# power.net
KiCad netlist of a schematic drawn in Altium Designer
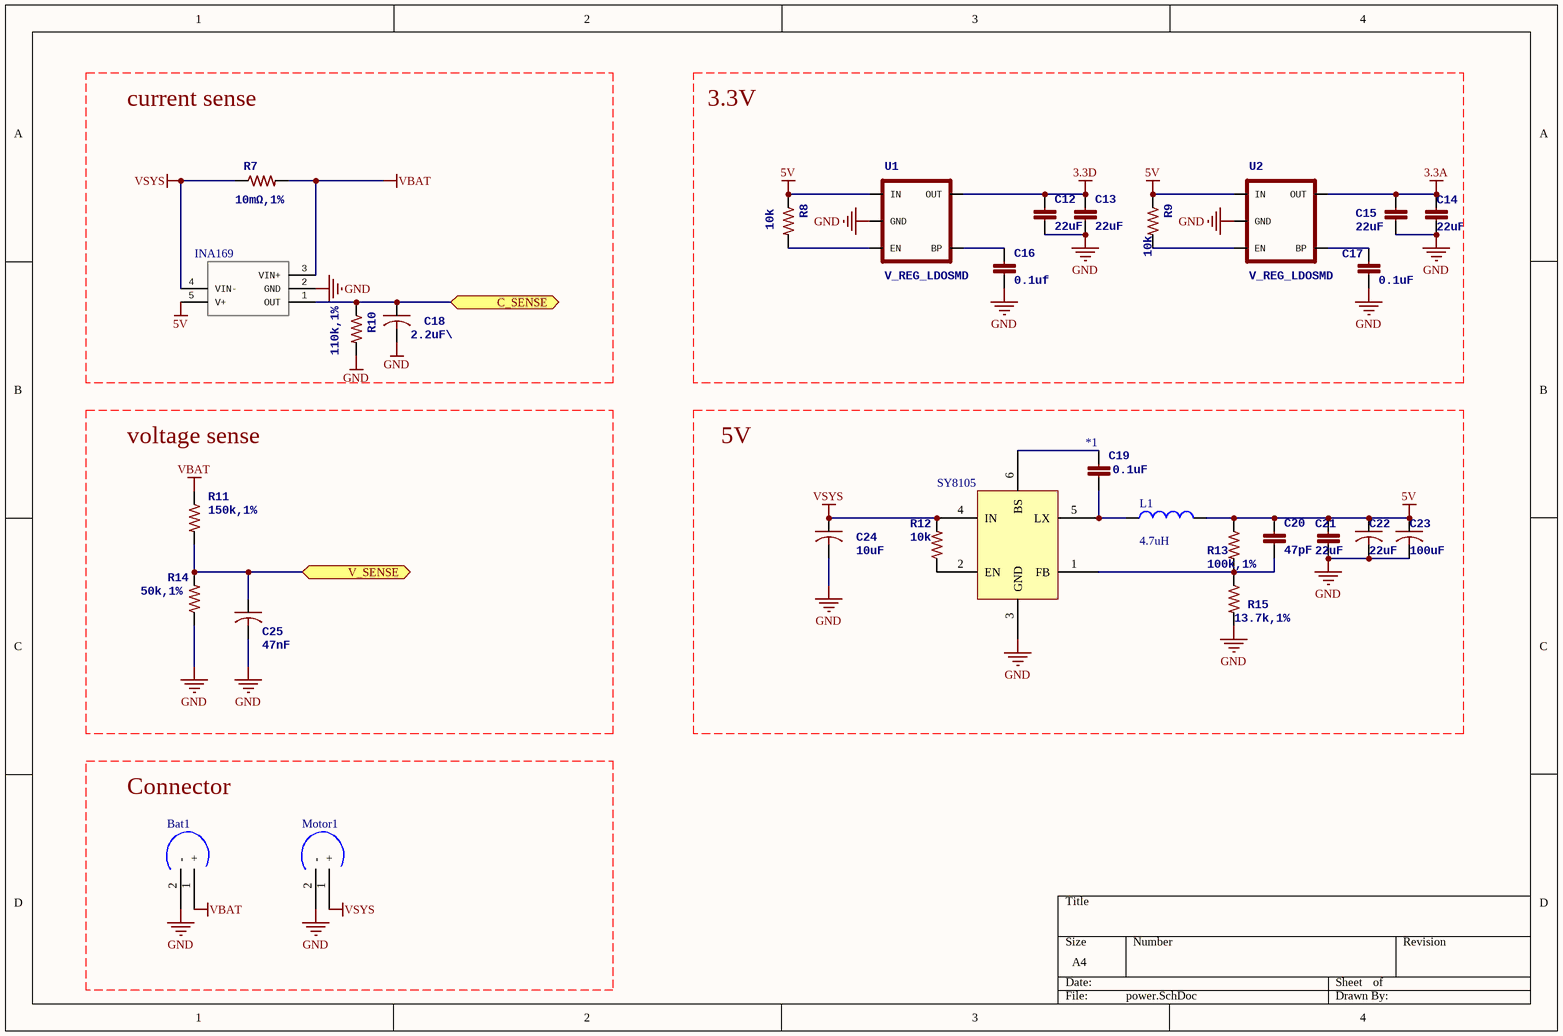
[diagram p0: power.SchDoc]

(export (version "E")
  (design (tool "Eeschema 10.0.6"))
  (components
    (comp (ref "*1") (value "SY8105") (footprint "SOT23-6") (libsource (lib "sch") (part "SY8105")))
    (comp (ref "Bat1")
      (value "Battery_AWG12")
      (footprint "Battery_AWG12")
      (libsource (lib "sch") (part "Battery_AWG12"))
    )
    (comp (ref "C12")
      (value "22uF")
      (footprint "0805")
      (description "<b>Capacitor</b>\nStandard 0603 ceramic capacitor, and 0.1\" leaded capacitor.")
      (fields (field (name "PARTNO") "CC0402ZRY5V7BB104"))
      (libsource (lib "pixhawk2") (part "CAP0402-CAP"))
    )
    (comp (ref "C13")
      (value "22uF")
      (footprint "0805")
      (description "<b>Capacitor</b>\nStandard 0603 ceramic capacitor, and 0.1\" leaded capacitor.")
      (fields (field (name "PARTNO") "CC0402ZRY5V7BB104"))
      (libsource (lib "pixhawk2") (part "CAP0402-CAP"))
    )
    (comp (ref "C14")
      (value "22uF")
      (footprint "0805")
      (description "<b>Capacitor</b>\nStandard 0603 ceramic capacitor, and 0.1\" leaded capacitor.")
      (fields (field (name "PARTNO") "CC0402ZRY5V7BB104"))
      (libsource (lib "pixhawk2") (part "CAP0402-CAP"))
    )
    (comp (ref "C15")
      (value "22uF")
      (footprint "0805")
      (description "<b>Capacitor</b>\nStandard 0603 ceramic capacitor, and 0.1\" leaded capacitor.")
      (fields (field (name "PARTNO") "CC0402ZRY5V7BB104"))
      (libsource (lib "pixhawk2") (part "CAP0402-CAP"))
    )
    (comp (ref "C16")
      (value "0.1uf")
      (footprint "0402")
      (description "<b>Capacitor</b>\nStandard 0603 ceramic capacitor, and 0.1\" leaded capacitor.")
      (fields (field (name "PARTNO") "CC0402ZRY5V7BB104"))
      (libsource (lib "pixhawk2") (part "CAP0402-CAP"))
    )
    (comp (ref "C17")
      (value "0.1uF")
      (footprint "0402")
      (description "<b>Capacitor</b>\nStandard 0603 ceramic capacitor, and 0.1\" leaded capacitor.")
      (fields (field (name "PARTNO") "CC0402ZRY5V7BB104"))
      (libsource (lib "pixhawk2") (part "CAP0402-CAP"))
    )
    (comp (ref "C18")
      (value "2.2u~{F}")
      (footprint "0402")
      (description "<B>CAPACITOR</B>, American symbol")
      (libsource (lib "adafruit") (part "C-USC0402"))
    )
    (comp (ref "C19")
      (value "0.1uF")
      (footprint "0603")
      (description "<b>Capacitor</b>\nStandard 0603 ceramic capacitor, and 0.1\" leaded capacitor.")
      (fields (field (name "PARTNO") "CC0402ZRY5V7BB104"))
      (libsource (lib "pixhawk2") (part "CAP0402-CAP"))
    )
    (comp (ref "C20")
      (value "47pF")
      (footprint "0402")
      (description "<b>Capacitor</b>\nStandard 0603 ceramic capacitor, and 0.1\" leaded capacitor.")
      (fields (field (name "PARTNO") "CC0402ZRY5V7BB104"))
      (libsource (lib "pixhawk2") (part "CAP0402-CAP"))
    )
    (comp (ref "C21")
      (value "22uF")
      (footprint "0805")
      (description "<b>Capacitor</b>\nStandard 0603 ceramic capacitor, and 0.1\" leaded capacitor.")
      (fields (field (name "PARTNO") "CC0402ZRY5V7BB104"))
      (libsource (lib "pixhawk2") (part "CAP0402-CAP"))
    )
    (comp (ref "C22")
      (value "22uF")
      (footprint "0805")
      (description "<B>CAPACITOR</B>, American symbol")
      (libsource (lib "adafruit") (part "C-USC0402"))
    )
    (comp (ref "C23")
      (value "100uF")
      (footprint "1210")
      (description "<B>CAPACITOR</B>, American symbol")
      (libsource (lib "adafruit") (part "C-USC0402"))
    )
    (comp (ref "C24")
      (value "10uF")
      (footprint "0805")
      (description "<B>CAPACITOR</B>, American symbol")
      (libsource (lib "adafruit") (part "C-USC0402"))
    )
    (comp (ref "C25")
      (value "47nF")
      (footprint "0402")
      (description "<B>CAPACITOR</B>, American symbol")
      (libsource (lib "adafruit") (part "C-USC0402"))
    )
    (comp (ref "L1")
      (value "4.7uH")
      (footprint "L6028/L6045")
      (description "Inductor")
      (fields (field (name "PUBLISHER") "Altium Limited"))
      (libsource (lib "Miscellaneous Devices") (part "Inductor"))
    )
    (comp (ref "Motor1")
      (value "Battery_AWG12")
      (footprint "Battery_AWG12")
      (libsource (lib "sch") (part "Battery_AWG12"))
    )
    (comp (ref "R7") (value "10mΩ,1%") (footprint "2512") (libsource (lib "SparkFun") (part "CSS2725FTL250")))
    (comp (ref "R8")
      (value "10k")
      (footprint "0402")
      (description "<b>Resistor</b>\nBasic schematic elements and footprints for 0603, 1206, and PTH resistors.")
      (libsource (lib "SparkFun") (part "RESISTOR0402-RES"))
    )
    (comp (ref "R9")
      (value "10k")
      (footprint "0402")
      (description "<b>Resistor</b>\nBasic schematic elements and footprints for 0603, 1206, and PTH resistors.")
      (libsource (lib "SparkFun") (part "RESISTOR0402-RES"))
    )
    (comp (ref "R10")
      (value "110k,1%")
      (footprint "0402")
      (description "<b>Resistor</b>\nBasic schematic elements and footprints for 0603, 1206, and PTH resistors.")
      (libsource (lib "SparkFun") (part "RESISTOR0402-RES"))
    )
    (comp (ref "R11")
      (value "150k,1%")
      (footprint "0402")
      (description "<b>Resistor</b>\nBasic schematic elements and footprints for 0603, 1206, and PTH resistors.")
      (libsource (lib "SparkFun") (part "RESISTOR0402-RES"))
    )
    (comp (ref "R12")
      (value "10k")
      (footprint "0402")
      (description "<b>Resistor</b>\nBasic schematic elements and footprints for 0603, 1206, and PTH resistors.")
      (libsource (lib "SparkFun") (part "RESISTOR0402-RES"))
    )
    (comp (ref "R13")
      (value "100k,1%")
      (footprint "0402")
      (description "<b>Resistor</b>\nBasic schematic elements and footprints for 0603, 1206, and PTH resistors.")
      (libsource (lib "SparkFun") (part "RESISTOR0402-RES"))
    )
    (comp (ref "R14")
      (value "50k,1%")
      (footprint "0402")
      (description "<b>Resistor</b>\nBasic schematic elements and footprints for 0603, 1206, and PTH resistors.")
      (libsource (lib "SparkFun") (part "RESISTOR0402-RES"))
    )
    (comp (ref "R15")
      (value "13.7k,1%")
      (footprint "0402")
      (description "<b>Resistor</b>\nBasic schematic elements and footprints for 0603, 1206, and PTH resistors.")
      (libsource (lib "SparkFun") (part "RESISTOR0402-RES"))
    )
    (comp (ref "U$1") (value "INA169") (footprint "SOT23-5") (libsource (lib "SparkFun") (part "INA169")))
    (comp (ref "U1")
      (value "V_REG_LDOSMD")
      (footprint "SOT23-5")
      (fields (field (name "PARTNO") "MIC5207-3.3YM5"))
      (libsource (lib "pixhawk2") (part "V_REG_LDOSMD"))
    )
    (comp (ref "U2")
      (value "V_REG_LDOSMD")
      (footprint "SOT23-5")
      (fields (field (name "PARTNO") "MIC5207-3.3YM5"))
      (libsource (lib "pixhawk2") (part "V_REG_LDOSMD"))
    )
  )
  (nets
    (net (code "1") (name "/C_SENSE") (class "Default")
      (node (ref "C18") (pin "1") (pinfunction "1_1") (pintype "passive"))
      (node (ref "R10") (pin "1") (pinfunction "1_1") (pintype "passive"))
      (node (ref "U$1") (pin "1") (pinfunction "OUT_1") (pintype "passive"))
    )
    (net (code "2") (name "/V_SENSE") (class "Default")
      (node (ref "C25") (pin "1") (pinfunction "1_1") (pintype "passive"))
      (node (ref "R11") (pin "2") (pinfunction "2_2") (pintype "passive"))
      (node (ref "R14") (pin "2") (pinfunction "2_2") (pintype "passive"))
    )
    (net (code "3") (name "3.3A") (class "Default")
      (node (ref "C14") (pin "1") (pinfunction "1_1") (pintype "passive"))
      (node (ref "C15") (pin "1") (pinfunction "1_1") (pintype "passive"))
      (node (ref "U2") (pin "5") (pinfunction "OUT_5") (pintype "passive"))
    )
    (net (code "4") (name "3.3D") (class "Default")
      (node (ref "C12") (pin "1") (pinfunction "1_1") (pintype "passive"))
      (node (ref "C13") (pin "1") (pinfunction "1_1") (pintype "passive"))
      (node (ref "U1") (pin "5") (pinfunction "OUT_5") (pintype "passive"))
    )
    (net (code "5") (name "5V") (class "Default")
      (node (ref "C20") (pin "1") (pinfunction "1_1") (pintype "passive"))
      (node (ref "C21") (pin "1") (pinfunction "1_1") (pintype "passive"))
      (node (ref "C22") (pin "1") (pinfunction "1_1") (pintype "passive"))
      (node (ref "C23") (pin "1") (pinfunction "1_1") (pintype "passive"))
      (node (ref "L1") (pin "2") (pinfunction "2_2") (pintype "passive"))
      (node (ref "R13") (pin "1") (pinfunction "1_1") (pintype "passive"))
      (node (ref "R8") (pin "1") (pinfunction "1_1") (pintype "passive"))
      (node (ref "R9") (pin "1") (pinfunction "1_1") (pintype "passive"))
      (node (ref "U$1") (pin "5") (pinfunction "V+_5") (pintype "passive"))
      (node (ref "U1") (pin "1") (pinfunction "IN_1") (pintype "passive"))
      (node (ref "U2") (pin "1") (pinfunction "IN_1") (pintype "passive"))
    )
    (net (code "6") (name "GND") (class "Default")
      (node (ref "*1") (pin "3") (pinfunction "GND_3") (pintype "passive"))
      (node (ref "Bat1") (pin "2") (pinfunction "-_2") (pintype "passive"))
      (node (ref "C12") (pin "2") (pinfunction "2_2") (pintype "passive"))
      (node (ref "C13") (pin "2") (pinfunction "2_2") (pintype "passive"))
      (node (ref "C14") (pin "2") (pinfunction "2_2") (pintype "passive"))
      (node (ref "C15") (pin "2") (pinfunction "2_2") (pintype "passive"))
      (node (ref "C16") (pin "2") (pinfunction "2_2") (pintype "passive"))
      (node (ref "C17") (pin "2") (pinfunction "2_2") (pintype "passive"))
      (node (ref "C18") (pin "2") (pinfunction "2_2") (pintype "passive"))
      (node (ref "C21") (pin "2") (pinfunction "2_2") (pintype "passive"))
      (node (ref "C22") (pin "2") (pinfunction "2_2") (pintype "passive"))
      (node (ref "C23") (pin "2") (pinfunction "2_2") (pintype "passive"))
      (node (ref "C24") (pin "2") (pinfunction "2_2") (pintype "passive"))
      (node (ref "C25") (pin "2") (pinfunction "2_2") (pintype "passive"))
      (node (ref "Motor1") (pin "2") (pinfunction "-_2") (pintype "passive"))
      (node (ref "R10") (pin "2") (pinfunction "2_2") (pintype "passive"))
      (node (ref "R14") (pin "1") (pinfunction "1_1") (pintype "passive"))
      (node (ref "R15") (pin "2") (pinfunction "2_2") (pintype "passive"))
      (node (ref "U$1") (pin "2") (pinfunction "GND_2") (pintype "passive"))
      (node (ref "U1") (pin "2") (pinfunction "GND_2") (pintype "passive"))
      (node (ref "U2") (pin "2") (pinfunction "GND_2") (pintype "passive"))
    )
    (net (code "7") (name "Net-(*1-BS)") (class "Default")
      (node (ref "*1") (pin "6") (pinfunction "BS_6") (pintype "passive"))
      (node (ref "C19") (pin "1") (pinfunction "1_1") (pintype "passive"))
    )
    (net (code "8") (name "Net-(*1-EN)") (class "Default")
      (node (ref "*1") (pin "2") (pinfunction "EN_2") (pintype "passive"))
      (node (ref "R12") (pin "1") (pinfunction "1_1") (pintype "passive"))
    )
    (net (code "9") (name "Net-(*1-FB)") (class "Default")
      (node (ref "*1") (pin "1") (pinfunction "FB_1") (pintype "passive"))
      (node (ref "C20") (pin "2") (pinfunction "2_2") (pintype "passive"))
      (node (ref "R13") (pin "2") (pinfunction "2_2") (pintype "passive"))
      (node (ref "R15") (pin "1") (pinfunction "1_1") (pintype "passive"))
    )
    (net (code "10") (name "Net-(*1-LX)") (class "Default")
      (node (ref "*1") (pin "5") (pinfunction "LX_5") (pintype "passive"))
      (node (ref "C19") (pin "2") (pinfunction "2_2") (pintype "passive"))
      (node (ref "L1") (pin "1") (pinfunction "1_1") (pintype "passive"))
    )
    (net (code "11") (name "Net-(U1-BP)") (class "Default")
      (node (ref "C16") (pin "1") (pinfunction "1_1") (pintype "passive"))
      (node (ref "U1") (pin "4") (pinfunction "BP_4") (pintype "passive"))
    )
    (net (code "12") (name "Net-(U1-EN)") (class "Default")
      (node (ref "R8") (pin "2") (pinfunction "2_2") (pintype "passive"))
      (node (ref "U1") (pin "3") (pinfunction "EN_3") (pintype "passive"))
    )
    (net (code "13") (name "Net-(U2-BP)") (class "Default")
      (node (ref "C17") (pin "1") (pinfunction "1_1") (pintype "passive"))
      (node (ref "U2") (pin "4") (pinfunction "BP_4") (pintype "passive"))
    )
    (net (code "14") (name "Net-(U2-EN)") (class "Default")
      (node (ref "R9") (pin "2") (pinfunction "2_2") (pintype "passive"))
      (node (ref "U2") (pin "3") (pinfunction "EN_3") (pintype "passive"))
    )
    (net (code "15") (name "VBAT") (class "Default")
      (node (ref "Bat1") (pin "1") (pinfunction "+_1") (pintype "passive"))
      (node (ref "R11") (pin "1") (pinfunction "1_1") (pintype "passive"))
      (node (ref "R7") (pin "P$2") (pinfunction "2_P$2") (pintype "passive"))
      (node (ref "U$1") (pin "3") (pinfunction "VIN+_3") (pintype "passive"))
    )
    (net (code "16") (name "VSYS") (class "Default")
      (node (ref "*1") (pin "4") (pinfunction "IN_4") (pintype "passive"))
      (node (ref "C24") (pin "1") (pinfunction "1_1") (pintype "passive"))
      (node (ref "Motor1") (pin "1") (pinfunction "+_1") (pintype "passive"))
      (node (ref "R12") (pin "2") (pinfunction "2_2") (pintype "passive"))
      (node (ref "R7") (pin "P$1") (pinfunction "1_P$1") (pintype "passive"))
      (node (ref "U$1") (pin "4") (pinfunction "VIN-_4") (pintype "passive"))
    )
  )
)
